# vDAC2.net
KiCad netlist of a schematic drawn in Altium Designer
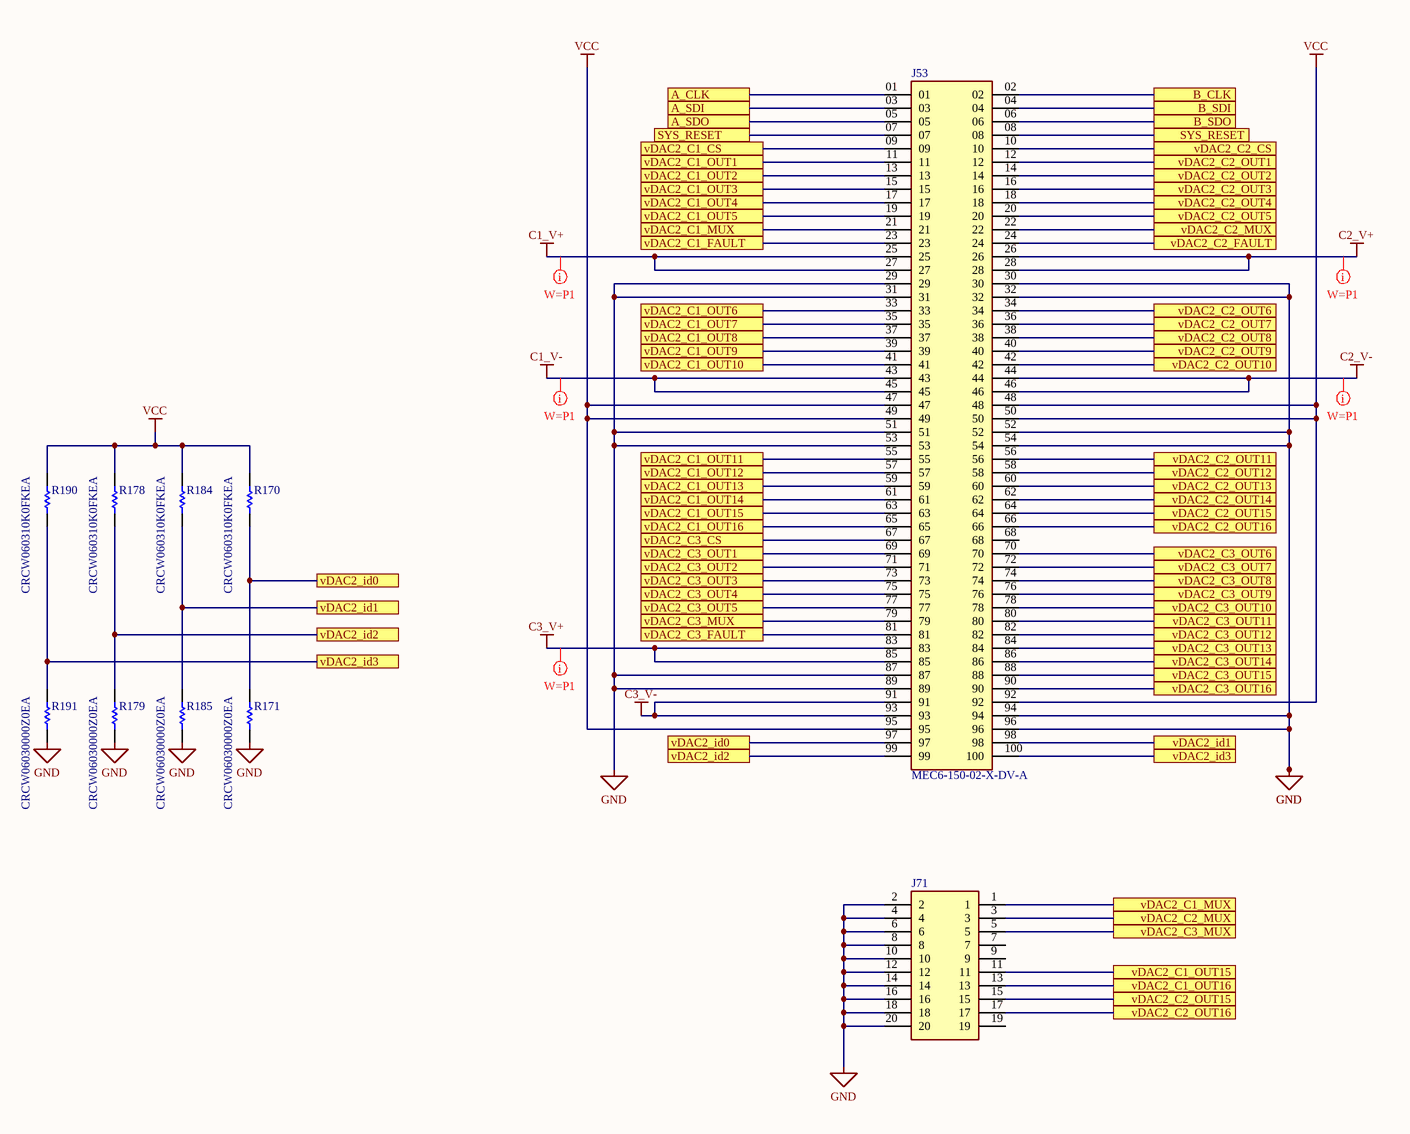
[diagram p0: vDAC2.SchDoc]

(export (version "E")
  (design (tool "Eeschema 10.0.6"))
  (components
    (comp (ref "J53")
      (value "MEC6-150-02-X-DV-A")
      (footprint "SAMTEC_MEC6-150-02-X-DV-A")
      (fields (field (name "MF") "Samtec"))
      (libsource (lib "xDAC_Carrier") (part "MEC6-150-02-X-DV-A"))
    )
    (comp (ref "J71")
      (value "~")
      (footprint "HDRV20W40P127_2X10_1270X340X550P")
      (description "Connector")
      (fields (field (name "MANUFACTURER_PART_NUMBER") "20021111-00020T4LF"))
      (libsource (lib "xDAC_Carrier") (part "20021111-00020T4LF"))
    )
    (comp (ref "R170")
      (value "CRCW060310K0FKEA")
      (footprint "RESC1609X50X30NL8T20")
      (description "Chip Resistor, 10 KOhm, +/- 1%, 100 mW, -55 to 155 degC, 0603 (1608 Metric), RoHS, Tape and Reel")
      (fields (field (name "MANUFACTURER") "Vishay Semiconductor"))
      (libsource (lib "Altium Content Vault") (part "RES-2"))
    )
    (comp (ref "R171")
      (value "CRCW06030000Z0EA")
      (footprint "RESC1609X50X30NL8T20")
      (description "Chip Resistor, 0 Ohm, Jumper, 100 mW, -55 to 155 degC, 0603 (1608 Metric), RoHS, Tape and Reel")
      (fields (field (name "MANUFACTURER") "Vishay Semiconductor"))
      (libsource (lib "Altium Content Vault") (part "RES-2"))
    )
    (comp (ref "R178")
      (value "CRCW060310K0FKEA")
      (footprint "RESC1609X50X30NL8T20")
      (description "Chip Resistor, 10 KOhm, +/- 1%, 100 mW, -55 to 155 degC, 0603 (1608 Metric), RoHS, Tape and Reel")
      (fields (field (name "MANUFACTURER") "Vishay Semiconductor"))
      (libsource (lib "Altium Content Vault") (part "RES-2"))
    )
    (comp (ref "R179")
      (value "CRCW06030000Z0EA")
      (footprint "RESC1609X50X30NL8T20")
      (description "Chip Resistor, 0 Ohm, Jumper, 100 mW, -55 to 155 degC, 0603 (1608 Metric), RoHS, Tape and Reel")
      (fields (field (name "MANUFACTURER") "Vishay Semiconductor"))
      (libsource (lib "Altium Content Vault") (part "RES-2"))
    )
    (comp (ref "R184")
      (value "CRCW060310K0FKEA")
      (footprint "RESC1609X50X30NL8T20")
      (description "Chip Resistor, 10 KOhm, +/- 1%, 100 mW, -55 to 155 degC, 0603 (1608 Metric), RoHS, Tape and Reel")
      (fields (field (name "MANUFACTURER") "Vishay Semiconductor"))
      (libsource (lib "Altium Content Vault") (part "RES-2"))
    )
    (comp (ref "R185")
      (value "CRCW06030000Z0EA")
      (footprint "RESC1609X50X30NL8T20")
      (description "Chip Resistor, 0 Ohm, Jumper, 100 mW, -55 to 155 degC, 0603 (1608 Metric), RoHS, Tape and Reel")
      (fields (field (name "MANUFACTURER") "Vishay Semiconductor"))
      (libsource (lib "Altium Content Vault") (part "RES-2"))
    )
    (comp (ref "R190")
      (value "CRCW060310K0FKEA")
      (footprint "RESC1609X50X30NL8T20")
      (description "Chip Resistor, 10 KOhm, +/- 1%, 100 mW, -55 to 155 degC, 0603 (1608 Metric), RoHS, Tape and Reel")
      (fields (field (name "MANUFACTURER") "Vishay Semiconductor"))
      (libsource (lib "Altium Content Vault") (part "RES-2"))
    )
    (comp (ref "R191")
      (value "CRCW06030000Z0EA")
      (footprint "RESC1609X50X30NL8T20")
      (description "Chip Resistor, 0 Ohm, Jumper, 100 mW, -55 to 155 degC, 0603 (1608 Metric), RoHS, Tape and Reel")
      (fields (field (name "MANUFACTURER") "Vishay Semiconductor"))
      (libsource (lib "Altium Content Vault") (part "RES-2"))
    )
  )
  (nets
    (net (code "1") (name "/A_CLK") (class "Default")
      (node (ref "J53") (pin "01") (pinfunction "01_01") (pintype "passive"))
    )
    (net (code "2") (name "/A_SDI") (class "Default")
      (node (ref "J53") (pin "03") (pinfunction "03_03") (pintype "passive"))
    )
    (net (code "3") (name "/A_SDO") (class "Default")
      (node (ref "J53") (pin "05") (pinfunction "05_05") (pintype "passive"))
    )
    (net (code "4") (name "/B_CLK") (class "Default")
      (node (ref "J53") (pin "02") (pinfunction "02_02") (pintype "passive"))
    )
    (net (code "5") (name "/B_SDI") (class "Default")
      (node (ref "J53") (pin "04") (pinfunction "04_04") (pintype "passive"))
    )
    (net (code "6") (name "/B_SDO") (class "Default")
      (node (ref "J53") (pin "06") (pinfunction "06_06") (pintype "passive"))
    )
    (net (code "7") (name "/SYS_RESET") (class "Default")
      (node (ref "J53") (pin "07") (pinfunction "07_07") (pintype "passive"))
      (node (ref "J53") (pin "08") (pinfunction "08_08") (pintype "passive"))
    )
    (net (code "8") (name "/vDAC2_C1_CS") (class "Default")
      (node (ref "J53") (pin "09") (pinfunction "09_09") (pintype "passive"))
    )
    (net (code "9") (name "/vDAC2_C1_FAULT") (class "Default")
      (node (ref "J53") (pin "23") (pinfunction "23_23") (pintype "passive"))
    )
    (net (code "10") (name "/vDAC2_C1_MUX") (class "Default")
      (node (ref "J53") (pin "21") (pinfunction "21_21") (pintype "passive"))
      (node (ref "J71") (pin "1") (pinfunction "1_1") (pintype "passive"))
    )
    (net (code "11") (name "/vDAC2_C1_OUT1") (class "Default")
      (node (ref "J53") (pin "11") (pinfunction "11_11") (pintype "passive"))
    )
    (net (code "12") (name "/vDAC2_C1_OUT2") (class "Default")
      (node (ref "J53") (pin "13") (pinfunction "13_13") (pintype "passive"))
    )
    (net (code "13") (name "/vDAC2_C1_OUT3") (class "Default")
      (node (ref "J53") (pin "15") (pinfunction "15_15") (pintype "passive"))
    )
    (net (code "14") (name "/vDAC2_C1_OUT4") (class "Default")
      (node (ref "J53") (pin "17") (pinfunction "17_17") (pintype "passive"))
    )
    (net (code "15") (name "/vDAC2_C1_OUT5") (class "Default")
      (node (ref "J53") (pin "19") (pinfunction "19_19") (pintype "passive"))
    )
    (net (code "16") (name "/vDAC2_C1_OUT6") (class "Default")
      (node (ref "J53") (pin "33") (pinfunction "33_33") (pintype "passive"))
    )
    (net (code "17") (name "/vDAC2_C1_OUT7") (class "Default")
      (node (ref "J53") (pin "35") (pinfunction "35_35") (pintype "passive"))
    )
    (net (code "18") (name "/vDAC2_C1_OUT8") (class "Default")
      (node (ref "J53") (pin "37") (pinfunction "37_37") (pintype "passive"))
    )
    (net (code "19") (name "/vDAC2_C1_OUT9") (class "Default")
      (node (ref "J53") (pin "39") (pinfunction "39_39") (pintype "passive"))
    )
    (net (code "20") (name "/vDAC2_C1_OUT10") (class "Default")
      (node (ref "J53") (pin "41") (pinfunction "41_41") (pintype "passive"))
    )
    (net (code "21") (name "/vDAC2_C1_OUT11") (class "Default")
      (node (ref "J53") (pin "55") (pinfunction "55_55") (pintype "passive"))
    )
    (net (code "22") (name "/vDAC2_C1_OUT12") (class "Default")
      (node (ref "J53") (pin "57") (pinfunction "57_57") (pintype "passive"))
    )
    (net (code "23") (name "/vDAC2_C1_OUT13") (class "Default")
      (node (ref "J53") (pin "59") (pinfunction "59_59") (pintype "passive"))
    )
    (net (code "24") (name "/vDAC2_C1_OUT14") (class "Default")
      (node (ref "J53") (pin "61") (pinfunction "61_61") (pintype "passive"))
    )
    (net (code "25") (name "/vDAC2_C1_OUT15") (class "Default")
      (node (ref "J53") (pin "63") (pinfunction "63_63") (pintype "passive"))
      (node (ref "J71") (pin "11") (pinfunction "11_11") (pintype "passive"))
    )
    (net (code "26") (name "/vDAC2_C1_OUT16") (class "Default")
      (node (ref "J53") (pin "65") (pinfunction "65_65") (pintype "passive"))
      (node (ref "J71") (pin "13") (pinfunction "13_13") (pintype "passive"))
    )
    (net (code "27") (name "/vDAC2_C2_CS") (class "Default")
      (node (ref "J53") (pin "10") (pinfunction "10_10") (pintype "passive"))
    )
    (net (code "28") (name "/vDAC2_C2_FAULT") (class "Default")
      (node (ref "J53") (pin "24") (pinfunction "24_24") (pintype "passive"))
    )
    (net (code "29") (name "/vDAC2_C2_MUX") (class "Default")
      (node (ref "J53") (pin "22") (pinfunction "22_22") (pintype "passive"))
      (node (ref "J71") (pin "3") (pinfunction "3_3") (pintype "passive"))
    )
    (net (code "30") (name "/vDAC2_C2_OUT1") (class "Default")
      (node (ref "J53") (pin "12") (pinfunction "12_12") (pintype "passive"))
    )
    (net (code "31") (name "/vDAC2_C2_OUT2") (class "Default")
      (node (ref "J53") (pin "14") (pinfunction "14_14") (pintype "passive"))
    )
    (net (code "32") (name "/vDAC2_C2_OUT3") (class "Default")
      (node (ref "J53") (pin "16") (pinfunction "16_16") (pintype "passive"))
    )
    (net (code "33") (name "/vDAC2_C2_OUT4") (class "Default")
      (node (ref "J53") (pin "18") (pinfunction "18_18") (pintype "passive"))
    )
    (net (code "34") (name "/vDAC2_C2_OUT5") (class "Default")
      (node (ref "J53") (pin "20") (pinfunction "20_20") (pintype "passive"))
    )
    (net (code "35") (name "/vDAC2_C2_OUT6") (class "Default")
      (node (ref "J53") (pin "34") (pinfunction "34_34") (pintype "passive"))
    )
    (net (code "36") (name "/vDAC2_C2_OUT7") (class "Default")
      (node (ref "J53") (pin "36") (pinfunction "36_36") (pintype "passive"))
    )
    (net (code "37") (name "/vDAC2_C2_OUT8") (class "Default")
      (node (ref "J53") (pin "38") (pinfunction "38_38") (pintype "passive"))
    )
    (net (code "38") (name "/vDAC2_C2_OUT9") (class "Default")
      (node (ref "J53") (pin "40") (pinfunction "40_40") (pintype "passive"))
    )
    (net (code "39") (name "/vDAC2_C2_OUT10") (class "Default")
      (node (ref "J53") (pin "42") (pinfunction "42_42") (pintype "passive"))
    )
    (net (code "40") (name "/vDAC2_C2_OUT11") (class "Default")
      (node (ref "J53") (pin "56") (pinfunction "56_56") (pintype "passive"))
    )
    (net (code "41") (name "/vDAC2_C2_OUT12") (class "Default")
      (node (ref "J53") (pin "58") (pinfunction "58_58") (pintype "passive"))
    )
    (net (code "42") (name "/vDAC2_C2_OUT13") (class "Default")
      (node (ref "J53") (pin "60") (pinfunction "60_60") (pintype "passive"))
    )
    (net (code "43") (name "/vDAC2_C2_OUT14") (class "Default")
      (node (ref "J53") (pin "62") (pinfunction "62_62") (pintype "passive"))
    )
    (net (code "44") (name "/vDAC2_C2_OUT15") (class "Default")
      (node (ref "J53") (pin "64") (pinfunction "64_64") (pintype "passive"))
      (node (ref "J71") (pin "15") (pinfunction "15_15") (pintype "passive"))
    )
    (net (code "45") (name "/vDAC2_C2_OUT16") (class "Default")
      (node (ref "J53") (pin "66") (pinfunction "66_66") (pintype "passive"))
      (node (ref "J71") (pin "17") (pinfunction "17_17") (pintype "passive"))
    )
    (net (code "46") (name "/vDAC2_C3_CS") (class "Default")
      (node (ref "J53") (pin "67") (pinfunction "67_67") (pintype "passive"))
    )
    (net (code "47") (name "/vDAC2_C3_FAULT") (class "Default")
      (node (ref "J53") (pin "81") (pinfunction "81_81") (pintype "passive"))
    )
    (net (code "48") (name "/vDAC2_C3_MUX") (class "Default")
      (node (ref "J53") (pin "79") (pinfunction "79_79") (pintype "passive"))
      (node (ref "J71") (pin "5") (pinfunction "5_5") (pintype "passive"))
    )
    (net (code "49") (name "/vDAC2_C3_OUT1") (class "Default")
      (node (ref "J53") (pin "69") (pinfunction "69_69") (pintype "passive"))
    )
    (net (code "50") (name "/vDAC2_C3_OUT2") (class "Default")
      (node (ref "J53") (pin "71") (pinfunction "71_71") (pintype "passive"))
    )
    (net (code "51") (name "/vDAC2_C3_OUT3") (class "Default")
      (node (ref "J53") (pin "73") (pinfunction "73_73") (pintype "passive"))
    )
    (net (code "52") (name "/vDAC2_C3_OUT4") (class "Default")
      (node (ref "J53") (pin "75") (pinfunction "75_75") (pintype "passive"))
    )
    (net (code "53") (name "/vDAC2_C3_OUT5") (class "Default")
      (node (ref "J53") (pin "77") (pinfunction "77_77") (pintype "passive"))
    )
    (net (code "54") (name "/vDAC2_C3_OUT6") (class "Default")
      (node (ref "J53") (pin "70") (pinfunction "70_70") (pintype "passive"))
    )
    (net (code "55") (name "/vDAC2_C3_OUT7") (class "Default")
      (node (ref "J53") (pin "72") (pinfunction "72_72") (pintype "passive"))
    )
    (net (code "56") (name "/vDAC2_C3_OUT8") (class "Default")
      (node (ref "J53") (pin "74") (pinfunction "74_74") (pintype "passive"))
    )
    (net (code "57") (name "/vDAC2_C3_OUT9") (class "Default")
      (node (ref "J53") (pin "76") (pinfunction "76_76") (pintype "passive"))
    )
    (net (code "58") (name "/vDAC2_C3_OUT10") (class "Default")
      (node (ref "J53") (pin "78") (pinfunction "78_78") (pintype "passive"))
    )
    (net (code "59") (name "/vDAC2_C3_OUT11") (class "Default")
      (node (ref "J53") (pin "80") (pinfunction "80_80") (pintype "passive"))
    )
    (net (code "60") (name "/vDAC2_C3_OUT12") (class "Default")
      (node (ref "J53") (pin "82") (pinfunction "82_82") (pintype "passive"))
    )
    (net (code "61") (name "/vDAC2_C3_OUT13") (class "Default")
      (node (ref "J53") (pin "84") (pinfunction "84_84") (pintype "passive"))
    )
    (net (code "62") (name "/vDAC2_C3_OUT14") (class "Default")
      (node (ref "J53") (pin "86") (pinfunction "86_86") (pintype "passive"))
    )
    (net (code "63") (name "/vDAC2_C3_OUT15") (class "Default")
      (node (ref "J53") (pin "88") (pinfunction "88_88") (pintype "passive"))
    )
    (net (code "64") (name "/vDAC2_C3_OUT16") (class "Default")
      (node (ref "J53") (pin "90") (pinfunction "90_90") (pintype "passive"))
    )
    (net (code "65") (name "/vDAC2_id0") (class "Default")
      (node (ref "J53") (pin "97") (pinfunction "97_97") (pintype "passive"))
      (node (ref "R170") (pin "1") (pinfunction "1_1") (pintype "passive"))
      (node (ref "R171") (pin "2") (pinfunction "2_2") (pintype "passive"))
    )
    (net (code "66") (name "/vDAC2_id1") (class "Default")
      (node (ref "J53") (pin "98") (pinfunction "98_98") (pintype "passive"))
      (node (ref "R184") (pin "1") (pinfunction "1_1") (pintype "passive"))
      (node (ref "R185") (pin "2") (pinfunction "2_2") (pintype "passive"))
    )
    (net (code "67") (name "/vDAC2_id2") (class "Default")
      (node (ref "J53") (pin "99") (pinfunction "99_99") (pintype "passive"))
      (node (ref "R178") (pin "1") (pinfunction "1_1") (pintype "passive"))
      (node (ref "R179") (pin "2") (pinfunction "2_2") (pintype "passive"))
    )
    (net (code "68") (name "/vDAC2_id3") (class "Default")
      (node (ref "J53") (pin "100") (pinfunction "100_100") (pintype "passive"))
      (node (ref "R190") (pin "1") (pinfunction "1_1") (pintype "passive"))
      (node (ref "R191") (pin "2") (pinfunction "2_2") (pintype "passive"))
    )
    (net (code "69") (name "C1_V+") (class "Default")
      (node (ref "J53") (pin "25") (pinfunction "25_25") (pintype "passive"))
      (node (ref "J53") (pin "27") (pinfunction "27_27") (pintype "passive"))
    )
    (net (code "70") (name "C1_V-") (class "Default")
      (node (ref "J53") (pin "43") (pinfunction "43_43") (pintype "passive"))
      (node (ref "J53") (pin "45") (pinfunction "45_45") (pintype "passive"))
    )
    (net (code "71") (name "C2_V+") (class "Default")
      (node (ref "J53") (pin "26") (pinfunction "26_26") (pintype "passive"))
      (node (ref "J53") (pin "28") (pinfunction "28_28") (pintype "passive"))
    )
    (net (code "72") (name "C2_V-") (class "Default")
      (node (ref "J53") (pin "44") (pinfunction "44_44") (pintype "passive"))
      (node (ref "J53") (pin "46") (pinfunction "46_46") (pintype "passive"))
    )
    (net (code "73") (name "C3_V+") (class "Default")
      (node (ref "J53") (pin "83") (pinfunction "83_83") (pintype "passive"))
      (node (ref "J53") (pin "85") (pinfunction "85_85") (pintype "passive"))
    )
    (net (code "74") (name "C3_V-") (class "Default")
      (node (ref "J53") (pin "91") (pinfunction "91_91") (pintype "passive"))
      (node (ref "J53") (pin "93") (pinfunction "93_93") (pintype "passive"))
    )
    (net (code "75") (name "GND") (class "Default")
      (node (ref "J53") (pin "29") (pinfunction "29_29") (pintype "passive"))
      (node (ref "J53") (pin "30") (pinfunction "30_30") (pintype "passive"))
      (node (ref "J53") (pin "31") (pinfunction "31_31") (pintype "passive"))
      (node (ref "J53") (pin "32") (pinfunction "32_32") (pintype "passive"))
      (node (ref "J53") (pin "51") (pinfunction "51_51") (pintype "passive"))
      (node (ref "J53") (pin "52") (pinfunction "52_52") (pintype "passive"))
      (node (ref "J53") (pin "53") (pinfunction "53_53") (pintype "passive"))
      (node (ref "J53") (pin "54") (pinfunction "54_54") (pintype "passive"))
      (node (ref "J53") (pin "87") (pinfunction "87_87") (pintype "passive"))
      (node (ref "J53") (pin "89") (pinfunction "89_89") (pintype "passive"))
      (node (ref "J53") (pin "94") (pinfunction "94_94") (pintype "passive"))
      (node (ref "J53") (pin "96") (pinfunction "96_96") (pintype "passive"))
      (node (ref "J71") (pin "10") (pinfunction "10_10") (pintype "passive"))
      (node (ref "J71") (pin "12") (pinfunction "12_12") (pintype "passive"))
      (node (ref "J71") (pin "14") (pinfunction "14_14") (pintype "passive"))
      (node (ref "J71") (pin "16") (pinfunction "16_16") (pintype "passive"))
      (node (ref "J71") (pin "18") (pinfunction "18_18") (pintype "passive"))
      (node (ref "J71") (pin "2") (pinfunction "2_2") (pintype "passive"))
      (node (ref "J71") (pin "20") (pinfunction "20_20") (pintype "passive"))
      (node (ref "J71") (pin "4") (pinfunction "4_4") (pintype "passive"))
      (node (ref "J71") (pin "6") (pinfunction "6_6") (pintype "passive"))
      (node (ref "J71") (pin "8") (pinfunction "8_8") (pintype "passive"))
      (node (ref "R171") (pin "1") (pinfunction "1_1") (pintype "passive"))
      (node (ref "R179") (pin "1") (pinfunction "1_1") (pintype "passive"))
      (node (ref "R185") (pin "1") (pinfunction "1_1") (pintype "passive"))
      (node (ref "R191") (pin "1") (pinfunction "1_1") (pintype "passive"))
    )
    (net (code "76") (name "VCC") (class "Default")
      (node (ref "J53") (pin "47") (pinfunction "47_47") (pintype "passive"))
      (node (ref "J53") (pin "48") (pinfunction "48_48") (pintype "passive"))
      (node (ref "J53") (pin "49") (pinfunction "49_49") (pintype "passive"))
      (node (ref "J53") (pin "50") (pinfunction "50_50") (pintype "passive"))
      (node (ref "J53") (pin "92") (pinfunction "92_92") (pintype "passive"))
      (node (ref "J53") (pin "95") (pinfunction "95_95") (pintype "passive"))
      (node (ref "R170") (pin "2") (pinfunction "2_2") (pintype "passive"))
      (node (ref "R178") (pin "2") (pinfunction "2_2") (pintype "passive"))
      (node (ref "R184") (pin "2") (pinfunction "2_2") (pintype "passive"))
      (node (ref "R190") (pin "2") (pinfunction "2_2") (pintype "passive"))
    )
    (net (code "77") (name "unconnected-(J53-Pad68)") (class "Default")
      (node (ref "J53") (pin "68") (pinfunction "68_68") (pintype "passive"))
    )
    (net (code "78") (name "unconnected-(J71-Pad7)") (class "Default")
      (node (ref "J71") (pin "7") (pinfunction "7_7") (pintype "passive"))
    )
    (net (code "79") (name "unconnected-(J71-Pad9)") (class "Default")
      (node (ref "J71") (pin "9") (pinfunction "9_9") (pintype "passive"))
    )
    (net (code "80") (name "unconnected-(J71-Pad19)") (class "Default")
      (node (ref "J71") (pin "19") (pinfunction "19_19") (pintype "passive"))
    )
  )
)
